# current_source.net
KiCad netlist of a schematic drawn in Altium Designer
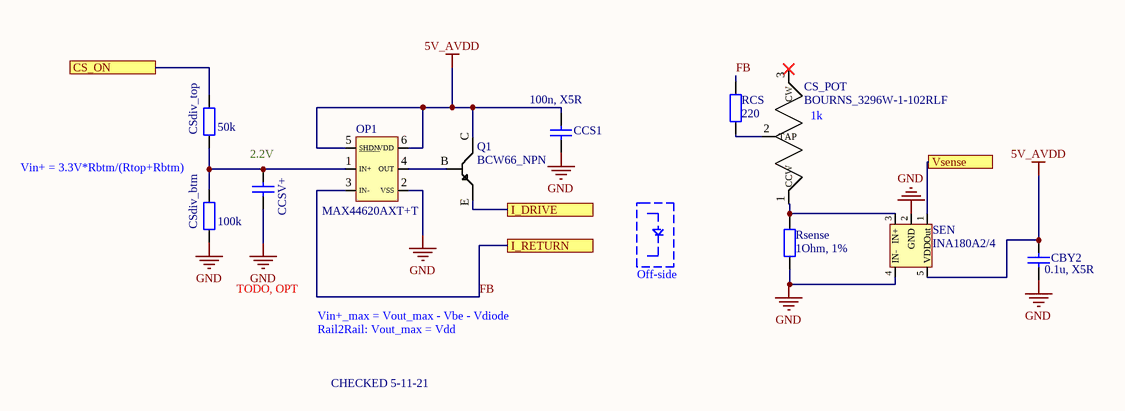
[diagram p0: current_source.SchDoc]

(export (version "E")
  (design (tool "Eeschema 10.0.6"))
  (components
    (comp (ref "CBY2")
      (value "0.1u, X5R")
      (footprint "1608[0603]")
      (description "Capacitor (Semiconductor SIM Model)")
      (fields (field (name "PUBLISHER") "Altium Limited"))
      (libsource (lib "Miscellaneous Devices") (part "Cap Semi"))
    )
    (comp (ref "CCS1")
      (value "100n, X5R")
      (footprint "1608[0603]")
      (description "Capacitor (Semiconductor SIM Model)")
      (fields (field (name "PUBLISHER") "Altium Limited"))
      (libsource (lib "Miscellaneous Devices") (part "Cap Semi"))
    )
    (comp (ref "CCSV+")
      (value "TODO, OPT")
      (footprint "1608[0603]")
      (description "Capacitor (Semiconductor SIM Model)")
      (fields (field (name "PUBLISHER") "Altium Limited"))
      (libsource (lib "Miscellaneous Devices") (part "Cap Semi"))
    )
    (comp (ref "CSdiv_btm")
      (value "100k")
      (footprint "WRIS-KSKE_0805")
      (description "WRIS-KSKE SMT Thick Film Resistor, size 0805, 0.1Ohm, 0.33W")
      (fields
        (field (name "MANUFACTURER") "Wurth Elektronik")
        (field (name "MANUFACTURER PART NUMBER") "560050320001")
      )
      (libsource (lib "Wurth_thick_film_resistors") (part "560050320001"))
    )
    (comp (ref "CSdiv_top")
      (value "50k")
      (footprint "WRIS-KSKE_0805")
      (description "WRIS-KSKE SMT Thick Film Resistor, size 0805, 0.1Ohm, 0.33W")
      (fields
        (field (name "MANUFACTURER") "Wurth Elektronik")
        (field (name "MANUFACTURER PART NUMBER") "560050320001")
      )
      (libsource (lib "Wurth_thick_film_resistors") (part "560050320001"))
    )
    (comp (ref "CS_POT")
      (value "BOURNS_3296W-1-102RLF")
      (footprint "BOURNS_3296W-1")
      (description "Vertical Potentiometer, multi-turn, 10%")
      (libsource (lib "Potentiometer") (part "BOURNS_3296W-1-104RLF"))
    )
    (comp (ref "OP1")
      (value "MAX44620AXT+T")
      (footprint "MAX44260_ATX+T")
      (description "Operationsverstärker 1.8V, 15MHz Low-Offs et, Low-Power, Rail")
      (libsource (lib "OP_Amps") (part "MAX44620AXT+T"))
    )
    (comp (ref "Q1")
      (value "BCW66_NPN")
      (footprint "BCW66_NPN")
      (libsource (lib "LaserDiode") (part "BCW66_NPN"))
    )
    (comp (ref "RCS")
      (value "220")
      (footprint "WRIS-KSKE_0805")
      (description "WRIS-KSKE SMT Thick Film Resistor, size 0805, 0.1Ohm, 0.33W")
      (fields
        (field (name "MANUFACTURER") "Wurth Elektronik")
        (field (name "MANUFACTURER PART NUMBER") "560050320001")
      )
      (libsource (lib "Wurth_thick_film_resistors") (part "560050320001"))
    )
    (comp (ref "Rsense")
      (value "1Ohm, 1%")
      (footprint "WRIS-KSKE_0603")
      (description "WRIS-KSKE SMT Thick Film Resistor, size 0603, 0.1Ohm, 0.25W")
      (fields
        (field (name "MANUFACTURER") "Wurth Elektronik")
        (field (name "MANUFACTURER PART NUMBER") "560050316001")
      )
      (libsource (lib "Wurth_thick_film_resistors") (part "560050316001"))
    )
    (comp (ref "SEN")
      (value "INA180A2/4")
      (footprint "INA180Ax")
      (description "INA180Ax Low- and High-SideVoltageOutput,Current-SenseAmplifiers")
      (libsource (lib "Regulator") (part "INA180Ax"))
    )
  )
  (nets
    (net (code "1") (name "/CS_ON") (class "Default")
      (node (ref "CSdiv_top") (pin "1") (pinfunction "1_1") (pintype "passive"))
    )
    (net (code "2") (name "/FB") (class "Default")
      (node (ref "OP1") (pin "3") (pinfunction "IN-_3") (pintype "passive"))
      (node (ref "RCS") (pin "1") (pinfunction "1_1") (pintype "passive"))
    )
    (net (code "3") (name "/I_DRIVE") (class "Default") (node (ref "Q1") (pin "E") (pintype "passive")))
    (net (code "4") (name "/Vsense") (class "Default")
      (node (ref "SEN") (pin "1") (pinfunction "Out_1") (pintype "passive"))
    )
    (net (code "5") (name "5V_AVDD") (class "Default")
      (node (ref "CBY2") (pin "1") (pinfunction "1_1") (pintype "passive"))
      (node (ref "CCS1") (pin "2") (pinfunction "2_2") (pintype "passive"))
      (node (ref "OP1") (pin "5") (pinfunction "SHDN_5") (pintype "passive"))
      (node (ref "OP1") (pin "6") (pinfunction "VDD_6") (pintype "passive"))
      (node (ref "Q1") (pin "C") (pintype "passive"))
      (node (ref "SEN") (pin "5") (pinfunction "VDD_5") (pintype "passive"))
    )
    (net (code "6") (name "GND") (class "Default")
      (node (ref "CBY2") (pin "2") (pinfunction "2_2") (pintype "passive"))
      (node (ref "CCS1") (pin "1") (pinfunction "1_1") (pintype "passive"))
      (node (ref "CCSV+") (pin "2") (pinfunction "2_2") (pintype "passive"))
      (node (ref "CSdiv_btm") (pin "2") (pinfunction "2_2") (pintype "passive"))
      (node (ref "OP1") (pin "2") (pinfunction "VSS_2") (pintype "passive"))
      (node (ref "Rsense") (pin "1") (pinfunction "1_1") (pintype "passive"))
      (node (ref "SEN") (pin "2") (pinfunction "GND_2") (pintype "passive"))
      (node (ref "SEN") (pin "4") (pinfunction "IN-_4") (pintype "passive"))
    )
    (net (code "7") (name "Net-(CS_POT-CCW)") (class "Default")
      (node (ref "CS_POT") (pin "1") (pinfunction "CCW_1") (pintype "passive"))
      (node (ref "Rsense") (pin "2") (pinfunction "2_2") (pintype "passive"))
      (node (ref "SEN") (pin "3") (pinfunction "IN+_3") (pintype "passive"))
    )
    (net (code "8") (name "Net-(CS_POT-TAP)") (class "Default")
      (node (ref "CS_POT") (pin "2") (pinfunction "TAP_2") (pintype "passive"))
      (node (ref "RCS") (pin "2") (pinfunction "2_2") (pintype "passive"))
    )
    (net (code "9") (name "Net-(OP1-IN+)") (class "Default")
      (node (ref "CCSV+") (pin "1") (pinfunction "1_1") (pintype "passive"))
      (node (ref "CSdiv_btm") (pin "1") (pinfunction "1_1") (pintype "passive"))
      (node (ref "CSdiv_top") (pin "2") (pinfunction "2_2") (pintype "passive"))
      (node (ref "OP1") (pin "1") (pinfunction "IN+_1") (pintype "passive"))
    )
    (net (code "10") (name "Net-(OP1-OUT)") (class "Default")
      (node (ref "OP1") (pin "4") (pinfunction "OUT_4") (pintype "passive"))
      (node (ref "Q1") (pin "B") (pintype "passive"))
    )
    (net (code "11") (name "unconnected-(CS_POT-CW-Pad3)") (class "Default")
      (node (ref "CS_POT") (pin "3") (pinfunction "CW_3") (pintype "passive+no_connect"))
    )
  )
)
